# New_Gyro_4_0_-_Interrogation_Board.net
KiCad netlist of a schematic drawn in Altium Designer
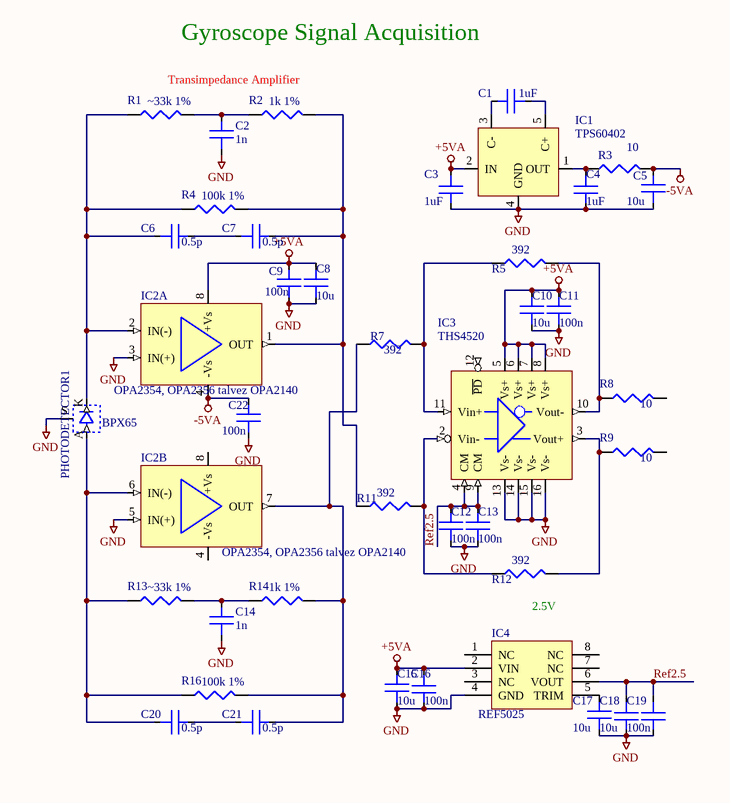
[diagram p0: New Gyro 4.0  - Interrogation Board.SchDoc]

(export (version "E")
  (design (tool "Eeschema 10.0.6"))
  (components
    (comp (ref "C1")
      (value "1uF")
      (footprint "0805-cap")
      (description "Capacitor Thick film")
      (libsource (lib "*") (part "CAP"))
    )
    (comp (ref "C2")
      (value "1n")
      (footprint "0805-cap")
      (description "Capacitor Thick film")
      (libsource (lib "*") (part "CAP"))
    )
    (comp (ref "C3")
      (value "1uF")
      (footprint "0805-cap")
      (description "Capacitor Thick film")
      (libsource (lib "*") (part "CAP"))
    )
    (comp (ref "C4")
      (value "1uF")
      (footprint "0805-cap")
      (description "Capacitor Thick film")
      (libsource (lib "*") (part "CAP"))
    )
    (comp (ref "C5")
      (value "10u")
      (footprint "0805-cap")
      (description "Capacitor Thick film")
      (libsource (lib "*") (part "CAP"))
    )
    (comp (ref "C6")
      (value "0.5p")
      (footprint "0805-cap")
      (description "Capacitor Thick film")
      (libsource (lib "*") (part "CAP"))
    )
    (comp (ref "C7")
      (value "0.5p")
      (footprint "0805-cap")
      (description "Capacitor Thick film")
      (libsource (lib "*") (part "CAP"))
    )
    (comp (ref "C8")
      (value "10u")
      (footprint "0805-cap")
      (description "Capacitor Thick film")
      (libsource (lib "*") (part "CAP"))
    )
    (comp (ref "C9")
      (value "100n")
      (footprint "0805-cap")
      (description "Capacitor Thick film")
      (libsource (lib "*") (part "CAP"))
    )
    (comp (ref "C10")
      (value "10u")
      (footprint "0805-cap")
      (description "Capacitor Thick film")
      (libsource (lib "*") (part "CAP"))
    )
    (comp (ref "C11")
      (value "100n")
      (footprint "0805-cap")
      (description "Capacitor Thick film")
      (libsource (lib "*") (part "CAP"))
    )
    (comp (ref "C12")
      (value "100n")
      (footprint "0805-cap")
      (description "Capacitor Thick film")
      (libsource (lib "*") (part "CAP"))
    )
    (comp (ref "C13")
      (value "100n")
      (footprint "0805-cap")
      (description "Capacitor Thick film")
      (libsource (lib "*") (part "CAP"))
    )
    (comp (ref "C14")
      (value "1n")
      (footprint "0805-cap")
      (description "Capacitor Thick film")
      (libsource (lib "*") (part "CAP"))
    )
    (comp (ref "C15")
      (value "10u")
      (footprint "0805-cap")
      (description "Capacitor Thick film")
      (libsource (lib "*") (part "CAP"))
    )
    (comp (ref "C16")
      (value "100n")
      (footprint "0805-cap")
      (description "Capacitor Thick film")
      (libsource (lib "*") (part "CAP"))
    )
    (comp (ref "C17")
      (value "10u")
      (footprint "0805-cap")
      (description "Capacitor Thick film")
      (libsource (lib "*") (part "CAP"))
    )
    (comp (ref "C18")
      (value "10u")
      (footprint "0805-cap")
      (description "Capacitor Thick film")
      (libsource (lib "*") (part "CAP"))
    )
    (comp (ref "C19")
      (value "100n")
      (footprint "0805-cap")
      (description "Capacitor Thick film")
      (libsource (lib "*") (part "CAP"))
    )
    (comp (ref "C20")
      (value "0.5p")
      (footprint "0805-cap")
      (description "Capacitor Thick film")
      (libsource (lib "*") (part "CAP"))
    )
    (comp (ref "C21")
      (value "0.5p")
      (footprint "0805-cap")
      (description "Capacitor Thick film")
      (libsource (lib "*") (part "CAP"))
    )
    (comp (ref "C22")
      (value "100n")
      (footprint "0805-cap")
      (description "Capacitor Thick film")
      (libsource (lib "*") (part "CAP"))
    )
    (comp (ref "IC1")
      (value "TPS60402")
      (footprint "PlacaGiro_atualizada:SOT-23-5")
      (description "Charge Pump Inverter")
      (libsource (lib "Gyro") (part "TPS60401"))
    )
    (comp (ref "IC2")
      (value "OPA2354, OPA2356 talvez OPA2140")
      (footprint "MSOP8")
      (libsource (lib "Gyro") (part "AMPOPDUAL"))
    )
    (comp (ref "IC3")
      (value "THS4520")
      (footprint "QFN16")
      (description "WIDEBAND, LOW-DISTORTION, FULLY DIFFERENTIAL AMPLIFIER")
      (libsource (lib "Gyro") (part "THS4520"))
    )
    (comp (ref "IC4") (value "REF5025") (footprint "MSOP8") (libsource (lib "Gyro") (part "ADR440AMZ")))
    (comp (ref "PHOTODETECTOR1") (value "BPX65") (footprint "otico") (libsource (lib "*") (part "BYW29-150")))
    (comp (ref "R1")
      (value "~33k 1%")
      (footprint "0805")
      (description "Resistor Thick film 1%")
      (libsource (lib "*") (part "R08"))
    )
    (comp (ref "R2")
      (value "1k 1%")
      (footprint "0805")
      (description "Resistor Thick film 1%")
      (libsource (lib "*") (part "R08"))
    )
    (comp (ref "R3")
      (value "10")
      (footprint "0805")
      (description "Resistor Thick film 1%")
      (libsource (lib "*") (part "R08"))
    )
    (comp (ref "R4")
      (value "100k 1%")
      (footprint "0805")
      (description "Resistor Thick film 1%")
      (libsource (lib "*") (part "R08"))
    )
    (comp (ref "R5")
      (value "392")
      (footprint "0805")
      (description "Resistor Thick film 1%")
      (libsource (lib "*") (part "R08"))
    )
    (comp (ref "R7")
      (value "392")
      (footprint "0805")
      (description "Resistor Thick film 1%")
      (libsource (lib "*") (part "R08"))
    )
    (comp (ref "R8")
      (value "10")
      (footprint "0805")
      (description "Resistor Thick film 1%")
      (libsource (lib "*") (part "R08"))
    )
    (comp (ref "R9")
      (value "10")
      (footprint "0805")
      (description "Resistor Thick film 1%")
      (libsource (lib "*") (part "R08"))
    )
    (comp (ref "R11")
      (value "392")
      (footprint "0805")
      (description "Resistor Thick film 1%")
      (libsource (lib "*") (part "R08"))
    )
    (comp (ref "R12")
      (value "392")
      (footprint "0805")
      (description "Resistor Thick film 1%")
      (libsource (lib "*") (part "R08"))
    )
    (comp (ref "R13")
      (value "~33k 1%")
      (footprint "0805")
      (description "Resistor Thick film 1%")
      (libsource (lib "*") (part "R08"))
    )
    (comp (ref "R14")
      (value "1k 1%")
      (footprint "0805")
      (description "Resistor Thick film 1%")
      (libsource (lib "*") (part "R08"))
    )
    (comp (ref "R16")
      (value "100k 1%")
      (footprint "0805")
      (description "Resistor Thick film 1%")
      (libsource (lib "*") (part "R08"))
    )
  )
  (nets
    (net (code "1") (name "+5VA") (class "Default")
      (node (ref "C10") (pin "1") (pinfunction "1_1") (pintype "passive"))
      (node (ref "C11") (pin "1") (pinfunction "1_1") (pintype "passive"))
      (node (ref "C15") (pin "1") (pinfunction "1_1") (pintype "passive"))
      (node (ref "C16") (pin "2") (pinfunction "2_2") (pintype "passive"))
      (node (ref "C3") (pin "2") (pinfunction "2_2") (pintype "passive"))
      (node (ref "C8") (pin "1") (pinfunction "1_1") (pintype "passive"))
      (node (ref "C9") (pin "1") (pinfunction "1_1") (pintype "passive"))
      (node (ref "IC1") (pin "2") (pinfunction "IN_2") (pintype "passive"))
      (node (ref "IC2") (pin "8") (pinfunction "+Vs_8") (pintype "power_in"))
      (node (ref "IC3") (pin "5") (pinfunction "Vs+_5") (pintype "power_in"))
      (node (ref "IC3") (pin "6") (pinfunction "Vs+_6") (pintype "power_in"))
      (node (ref "IC3") (pin "7") (pinfunction "Vs+_7") (pintype "power_in"))
      (node (ref "IC3") (pin "8") (pinfunction "Vs+_8") (pintype "power_in"))
      (node (ref "IC4") (pin "2") (pinfunction "VIN_2") (pintype "passive"))
    )
    (net (code "2") (name "-5VA") (class "Default")
      (node (ref "C22") (pin "1") (pinfunction "1_1") (pintype "passive"))
      (node (ref "C5") (pin "1") (pinfunction "1_1") (pintype "passive"))
      (node (ref "IC2") (pin "4") (pinfunction "-Vs_4") (pintype "power_in"))
      (node (ref "R3") (pin "2") (pinfunction "2_2") (pintype "passive"))
    )
    (net (code "3") (name "/Ref2.5") (class "Default")
      (node (ref "C12") (pin "1") (pinfunction "1_1") (pintype "passive"))
      (node (ref "C13") (pin "1") (pinfunction "1_1") (pintype "passive"))
      (node (ref "C18") (pin "2") (pinfunction "2_2") (pintype "passive"))
      (node (ref "C19") (pin "2") (pinfunction "2_2") (pintype "passive"))
      (node (ref "IC3") (pin "4") (pinfunction "CM_4") (pintype "input"))
      (node (ref "IC3") (pin "9") (pinfunction "CM_9") (pintype "input"))
      (node (ref "IC4") (pin "6") (pinfunction "VOUT_6") (pintype "passive"))
    )
    (net (code "4") (name "GND") (class "Default")
      (node (ref "C10") (pin "2") (pinfunction "2_2") (pintype "passive"))
      (node (ref "C11") (pin "2") (pinfunction "2_2") (pintype "passive"))
      (node (ref "C12") (pin "2") (pinfunction "2_2") (pintype "passive"))
      (node (ref "C13") (pin "2") (pinfunction "2_2") (pintype "passive"))
      (node (ref "C14") (pin "2") (pinfunction "2_2") (pintype "passive"))
      (node (ref "C15") (pin "2") (pinfunction "2_2") (pintype "passive"))
      (node (ref "C16") (pin "1") (pinfunction "1_1") (pintype "passive"))
      (node (ref "C17") (pin "2") (pinfunction "2_2") (pintype "passive"))
      (node (ref "C18") (pin "1") (pinfunction "1_1") (pintype "passive"))
      (node (ref "C19") (pin "1") (pinfunction "1_1") (pintype "passive"))
      (node (ref "C2") (pin "2") (pinfunction "2_2") (pintype "passive"))
      (node (ref "C22") (pin "2") (pinfunction "2_2") (pintype "passive"))
      (node (ref "C3") (pin "1") (pinfunction "1_1") (pintype "passive"))
      (node (ref "C4") (pin "1") (pinfunction "1_1") (pintype "passive"))
      (node (ref "C5") (pin "2") (pinfunction "2_2") (pintype "passive"))
      (node (ref "C8") (pin "2") (pinfunction "2_2") (pintype "passive"))
      (node (ref "C9") (pin "2") (pinfunction "2_2") (pintype "passive"))
      (node (ref "IC1") (pin "4") (pinfunction "GND_4") (pintype "passive"))
      (node (ref "IC2") (pin "3") (pinfunction "IN(+)_3") (pintype "input"))
      (node (ref "IC2") (pin "5") (pinfunction "IN(+)_5") (pintype "input"))
      (node (ref "IC3") (pin "13") (pinfunction "Vs-_13") (pintype "power_in"))
      (node (ref "IC3") (pin "14") (pinfunction "Vs-_14") (pintype "power_in"))
      (node (ref "IC3") (pin "15") (pinfunction "Vs-_15") (pintype "power_in"))
      (node (ref "IC3") (pin "16") (pinfunction "Vs-_16") (pintype "power_in"))
      (node (ref "IC4") (pin "4") (pinfunction "GND_4") (pintype "passive"))
      (node (ref "PHOTODETECTOR1") (pin "S") (pinfunction "S_S") (pintype "passive"))
    )
    (net (code "5") (name "Net-(C2-Pad1)") (class "Default")
      (node (ref "C2") (pin "1") (pinfunction "1_1") (pintype "passive"))
      (node (ref "R1") (pin "2") (pinfunction "2_2") (pintype "passive"))
      (node (ref "R2") (pin "1") (pinfunction "1_1") (pintype "passive"))
    )
    (net (code "6") (name "Net-(C6-Pad1)") (class "Default")
      (node (ref "C6") (pin "1") (pinfunction "1_1") (pintype "passive"))
      (node (ref "C7") (pin "2") (pinfunction "2_2") (pintype "passive"))
    )
    (net (code "7") (name "Net-(C14-Pad1)") (class "Default")
      (node (ref "C14") (pin "1") (pinfunction "1_1") (pintype "passive"))
      (node (ref "R13") (pin "2") (pinfunction "2_2") (pintype "passive"))
      (node (ref "R14") (pin "1") (pinfunction "1_1") (pintype "passive"))
    )
    (net (code "8") (name "Net-(C20-Pad1)") (class "Default")
      (node (ref "C20") (pin "1") (pinfunction "1_1") (pintype "passive"))
      (node (ref "C21") (pin "2") (pinfunction "2_2") (pintype "passive"))
    )
    (net (code "9") (name "Net-(IC1-C+)") (class "Default")
      (node (ref "C1") (pin "2") (pinfunction "2_2") (pintype "passive"))
      (node (ref "IC1") (pin "5") (pinfunction "C+_5") (pintype "passive"))
    )
    (net (code "10") (name "Net-(IC1-C-)") (class "Default")
      (node (ref "C1") (pin "1") (pinfunction "1_1") (pintype "passive"))
      (node (ref "IC1") (pin "3") (pinfunction "C-_3") (pintype "passive"))
    )
    (net (code "11") (name "Net-(IC1-OUT)") (class "Default")
      (node (ref "C4") (pin "2") (pinfunction "2_2") (pintype "passive"))
      (node (ref "IC1") (pin "1") (pinfunction "OUT_1") (pintype "passive"))
      (node (ref "R3") (pin "1") (pinfunction "1_1") (pintype "passive"))
    )
    (net (code "12") (name "Net-(IC2A-IN(-))") (class "Default")
      (node (ref "C6") (pin "2") (pinfunction "2_2") (pintype "passive"))
      (node (ref "IC2") (pin "2") (pinfunction "IN(-)_2") (pintype "input"))
      (node (ref "PHOTODETECTOR1") (pin "K") (pinfunction "K_K") (pintype "output"))
      (node (ref "R1") (pin "1") (pinfunction "1_1") (pintype "passive"))
      (node (ref "R4") (pin "1") (pinfunction "1_1") (pintype "passive"))
    )
    (net (code "13") (name "Net-(IC2A-OUT)") (class "Default")
      (node (ref "C7") (pin "1") (pinfunction "1_1") (pintype "passive"))
      (node (ref "IC2") (pin "1") (pinfunction "OUT_1") (pintype "output"))
      (node (ref "R11") (pin "1") (pinfunction "1_1") (pintype "passive"))
      (node (ref "R2") (pin "2") (pinfunction "2_2") (pintype "passive"))
      (node (ref "R4") (pin "2") (pinfunction "2_2") (pintype "passive"))
    )
    (net (code "14") (name "Net-(IC2B-IN(-))") (class "Default")
      (node (ref "C20") (pin "2") (pinfunction "2_2") (pintype "passive"))
      (node (ref "IC2") (pin "6") (pinfunction "IN(-)_6") (pintype "input"))
      (node (ref "PHOTODETECTOR1") (pin "A") (pinfunction "A_A") (pintype "input"))
      (node (ref "R13") (pin "1") (pinfunction "1_1") (pintype "passive"))
      (node (ref "R16") (pin "1") (pinfunction "1_1") (pintype "passive"))
    )
    (net (code "15") (name "Net-(IC2B-OUT)") (class "Default")
      (node (ref "C21") (pin "1") (pinfunction "1_1") (pintype "passive"))
      (node (ref "IC2") (pin "7") (pinfunction "OUT_7") (pintype "output"))
      (node (ref "R14") (pin "2") (pinfunction "2_2") (pintype "passive"))
      (node (ref "R16") (pin "2") (pinfunction "2_2") (pintype "passive"))
      (node (ref "R7") (pin "1") (pinfunction "1_1") (pintype "passive"))
    )
    (net (code "16") (name "Net-(IC3-Vin+)") (class "Default")
      (node (ref "IC3") (pin "11") (pinfunction "Vin+_11") (pintype "input"))
      (node (ref "R5") (pin "1") (pinfunction "1_1") (pintype "passive"))
      (node (ref "R7") (pin "2") (pinfunction "2_2") (pintype "passive"))
    )
    (net (code "17") (name "Net-(IC3-Vin-)") (class "Default")
      (node (ref "IC3") (pin "2") (pinfunction "Vin-_2") (pintype "input"))
      (node (ref "R11") (pin "2") (pinfunction "2_2") (pintype "passive"))
      (node (ref "R12") (pin "1") (pinfunction "1_1") (pintype "passive"))
    )
    (net (code "18") (name "Net-(IC3-Vout+)") (class "Default")
      (node (ref "IC3") (pin "3") (pinfunction "Vout+_3") (pintype "output"))
      (node (ref "R12") (pin "2") (pinfunction "2_2") (pintype "passive"))
      (node (ref "R9") (pin "1") (pinfunction "1_1") (pintype "passive"))
    )
    (net (code "19") (name "Net-(IC3-Vout-)") (class "Default")
      (node (ref "IC3") (pin "10") (pinfunction "Vout-_10") (pintype "output"))
      (node (ref "R5") (pin "2") (pinfunction "2_2") (pintype "passive"))
      (node (ref "R8") (pin "1") (pinfunction "1_1") (pintype "passive"))
    )
    (net (code "20") (name "Net-(IC4-TRIM)") (class "Default")
      (node (ref "C17") (pin "1") (pinfunction "1_1") (pintype "passive"))
      (node (ref "IC4") (pin "5") (pinfunction "TRIM_5") (pintype "passive"))
    )
    (net (code "21") (name "unconnected-(IC2B-+Vs-Pad8)") (class "Default")
      (node (ref "IC2") (pin "8") (pinfunction "+Vs_8") (pintype "power_in"))
    )
    (net (code "22") (name "unconnected-(IC2B--Vs-Pad4)") (class "Default")
      (node (ref "IC2") (pin "4") (pinfunction "-Vs_4") (pintype "power_in"))
    )
    (net (code "23") (name "unconnected-(IC3-~{PD}-Pad12)") (class "Default")
      (node (ref "IC3") (pin "12") (pinfunction "~{PD}_12") (pintype "input"))
    )
    (net (code "24") (name "unconnected-(IC4-NC-Pad1)") (class "Default")
      (node (ref "IC4") (pin "1") (pinfunction "NC_1") (pintype "passive"))
    )
    (net (code "25") (name "unconnected-(IC4-NC-Pad3)") (class "Default")
      (node (ref "IC4") (pin "3") (pinfunction "NC_3") (pintype "passive"))
    )
    (net (code "26") (name "unconnected-(IC4-NC-Pad7)") (class "Default")
      (node (ref "IC4") (pin "7") (pinfunction "NC_7") (pintype "passive"))
    )
    (net (code "27") (name "unconnected-(IC4-NC-Pad8)") (class "Default")
      (node (ref "IC4") (pin "8") (pinfunction "NC_8") (pintype "passive"))
    )
    (net (code "28") (name "unconnected-(R8-Pad2)") (class "Default")
      (node (ref "R8") (pin "2") (pinfunction "2_2") (pintype "passive"))
    )
    (net (code "29") (name "unconnected-(R9-Pad2)") (class "Default")
      (node (ref "R9") (pin "2") (pinfunction "2_2") (pintype "passive"))
    )
  )
)
